# Nick_Lester_Final.net
KiCad netlist of a schematic drawn in EAGLE
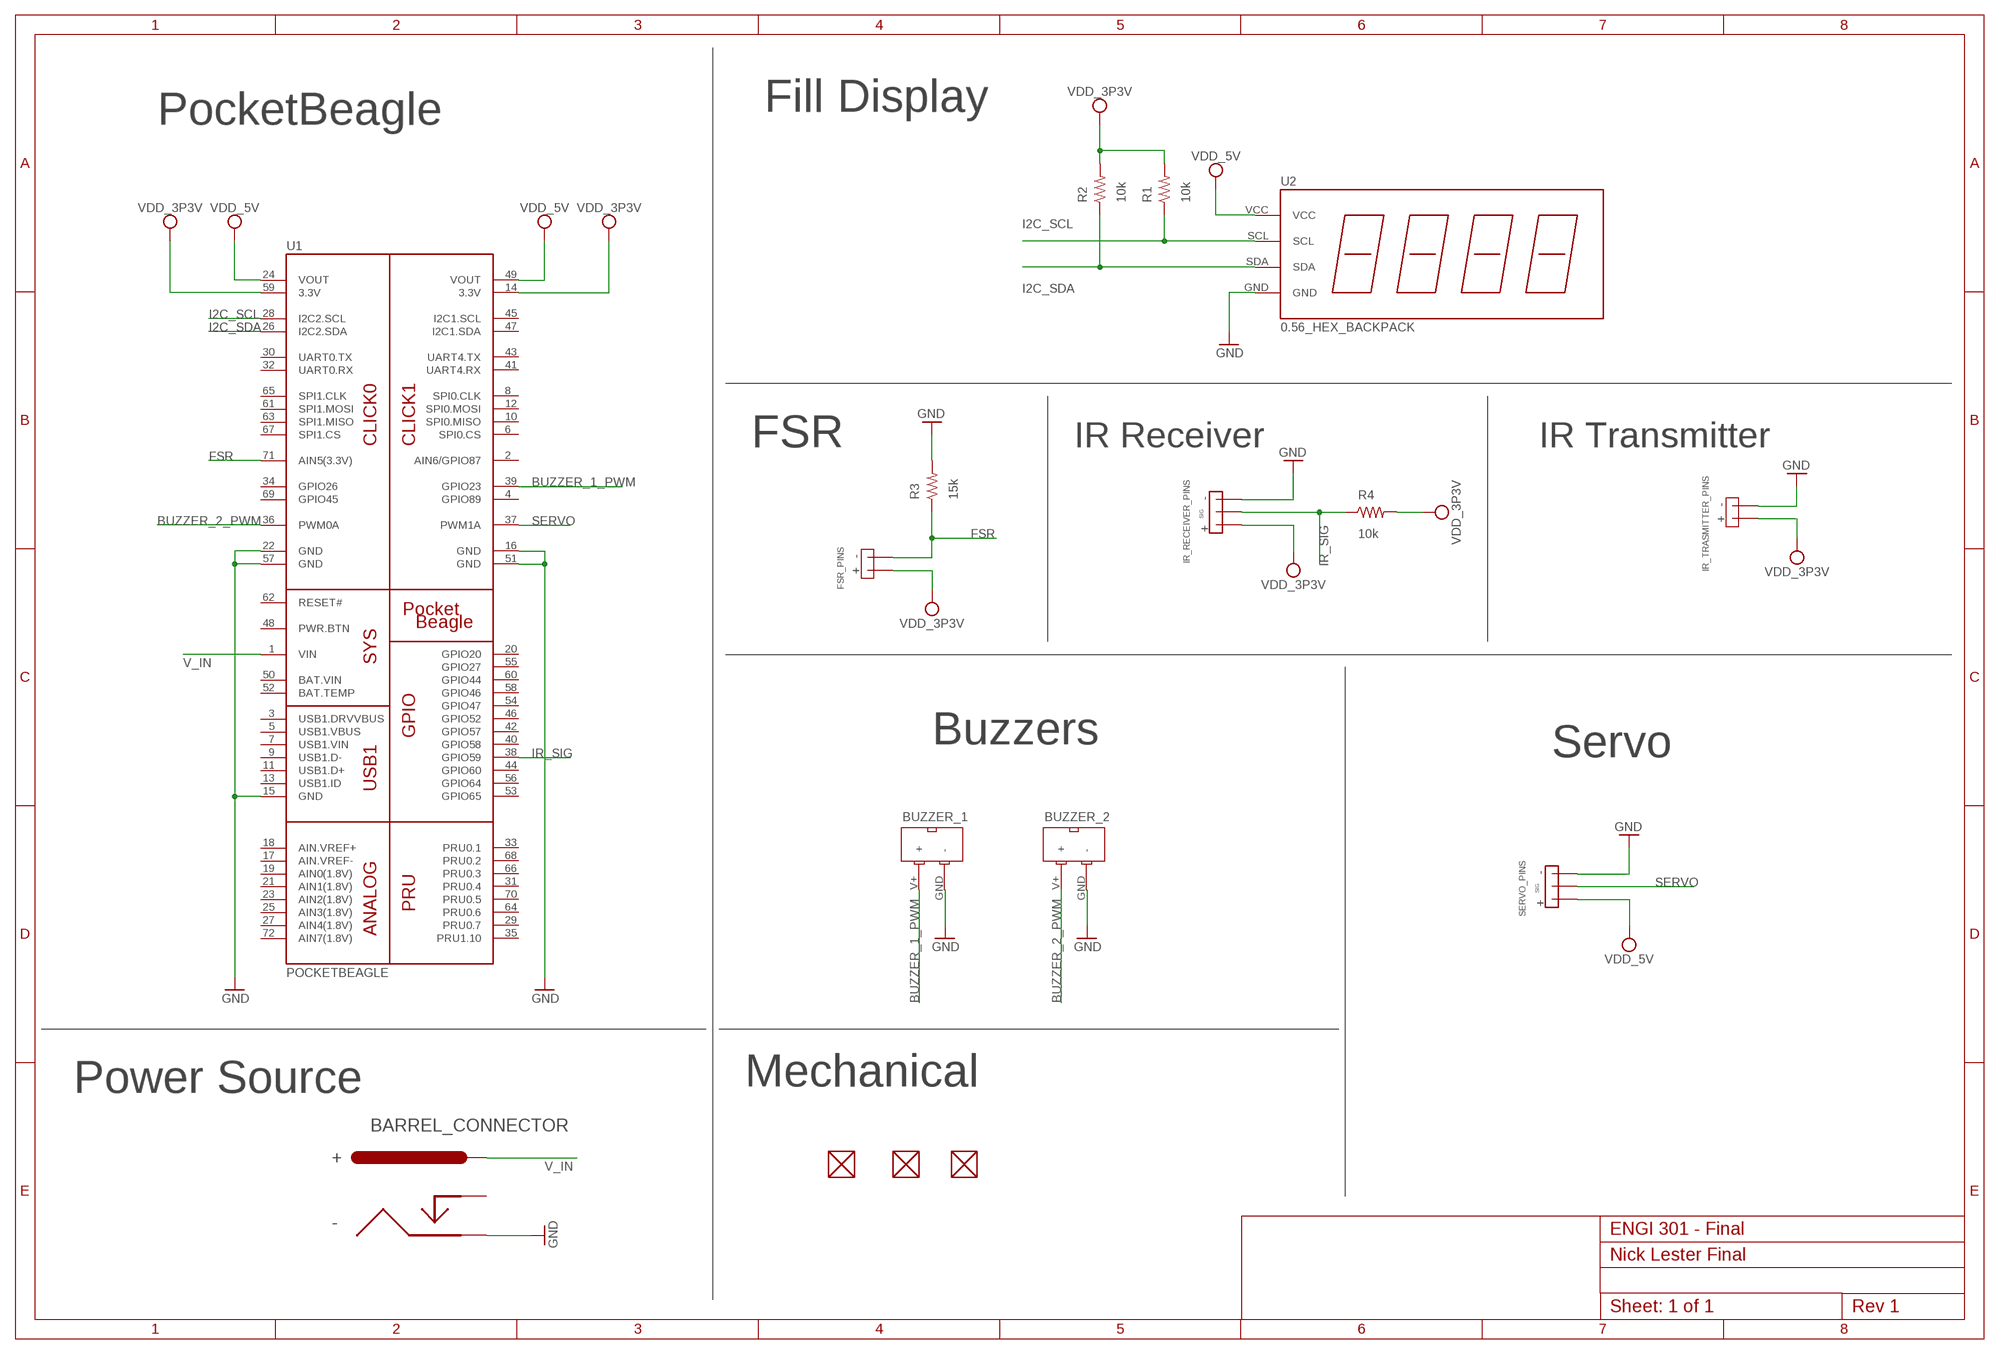
[diagram p0: schematic, sheet 1]

(export (version "E")
  (design (tool "Eeschema 10.0.6"))
  (components
    (comp (ref "BARREL_CONNECTOR")
      (value "BARREL_CONNECTOR")
      (footprint "eagle-import:BARREL_CONNECTOR")
      (libsource (lib "eagle-import") (part "BARREL_CONNECTOR"))
    )
    (comp (ref "BUZZER_1")
      (value "PS1240_BUZZER")
      (footprint "eagle-import:PS1240_BUZZER")
      (libsource (lib "eagle-import") (part "PS1240_BUZZER"))
    )
    (comp (ref "BUZZER_2")
      (value "PS1240_BUZZER")
      (footprint "eagle-import:PS1240_BUZZER")
      (libsource (lib "eagle-import") (part "PS1240_BUZZER"))
    )
    (comp (ref "FSR_PINS")
      (value "2_PIN_HEADER")
      (footprint "eagle-import:2_PIN_HEADER")
      (libsource (lib "eagle-import") (part "2_PIN_HEADER"))
    )
    (comp (ref "FUD1")
      (value "FIDUCIAL")
      (footprint "eagle-import:FIDUCIAL_40MIL")
      (libsource (lib "eagle-import") (part "FIDUCIAL"))
    )
    (comp (ref "FUD2")
      (value "FIDUCIAL")
      (footprint "eagle-import:FIDUCIAL_40MIL")
      (libsource (lib "eagle-import") (part "FIDUCIAL"))
    )
    (comp (ref "FUD3")
      (value "FIDUCIAL")
      (footprint "eagle-import:FIDUCIAL_40MIL")
      (libsource (lib "eagle-import") (part "FIDUCIAL"))
    )
    (comp (ref "IR_RECEIVER_PINS")
      (value "3_PIN_HEADER")
      (footprint "eagle-import:3_PIN_HEADER")
      (libsource (lib "eagle-import") (part "3_PIN_HEADER"))
    )
    (comp (ref "IR_TRASMITTER_PINS")
      (value "2_PIN_HEADER")
      (footprint "eagle-import:2_PIN_HEADER")
      (libsource (lib "eagle-import") (part "2_PIN_HEADER"))
    )
    (comp (ref "R1")
      (value "10k")
      (footprint "eagle-import:R0603")
      (libsource (lib "eagle-import") (part "R_R0603"))
    )
    (comp (ref "R2")
      (value "10k")
      (footprint "eagle-import:R0603")
      (libsource (lib "eagle-import") (part "R_R0603"))
    )
    (comp (ref "R3")
      (value "15k")
      (footprint "eagle-import:R0603")
      (libsource (lib "eagle-import") (part "R_R0603"))
    )
    (comp (ref "R4")
      (value "10k")
      (footprint "eagle-import:R0603")
      (libsource (lib "eagle-import") (part "R_R0603"))
    )
    (comp (ref "SERVO_PINS")
      (value "3_PIN_HEADER")
      (footprint "eagle-import:3_PIN_HEADER")
      (libsource (lib "eagle-import") (part "3_PIN_HEADER"))
    )
    (comp (ref "U1")
      (value "POCKETBEAGLE")
      (footprint "eagle-import:POCKETBEAGLE")
      (libsource (lib "eagle-import") (part "POCKETBEAGLE"))
    )
    (comp (ref "U2")
      (value "0.56_HEX_BACKPACK")
      (footprint "eagle-import:0.56_HEX_BACKPACK")
      (libsource (lib "eagle-import") (part "0.56_HEX_BACKPACK"))
    )
  )
  (nets
    (net (code "1") (name "/BAT.VIN") (class "Default")
      (node (ref "U1") (pin "50") (pinfunction "BAT.VIN_50") (pintype "power_in"))
    )
    (net (code "2") (name "/BUZZER_1_PWM") (class "Default")
      (node (ref "BUZZER_1") (pin "V+") (pinfunction "+_V+") (pintype "passive"))
      (node (ref "U1") (pin "39") (pinfunction "GPIO23_39") (pintype "bidirectional"))
    )
    (net (code "3") (name "/BUZZER_2_PWM") (class "Default")
      (node (ref "BUZZER_2") (pin "V+") (pinfunction "+_V+") (pintype "passive"))
      (node (ref "U1") (pin "36") (pinfunction "PWM0A_36") (pintype "bidirectional"))
    )
    (net (code "4") (name "/FSR") (class "Default")
      (node (ref "FSR_PINS") (pin "GND") (pinfunction "GND_GND") (pintype "bidirectional"))
      (node (ref "R3") (pin "1") (pinfunction "1_1") (pintype "passive"))
      (node (ref "U1") (pin "71") (pinfunction "AIN5(3.3V)_71") (pintype "bidirectional"))
    )
    (net (code "5") (name "/I2C_SCL") (class "Default")
      (node (ref "R1") (pin "1") (pinfunction "1_1") (pintype "passive"))
      (node (ref "U1") (pin "28") (pinfunction "I2C2.SCL_28") (pintype "bidirectional"))
      (node (ref "U2") (pin "SCL") (pinfunction "SCL_SCL") (pintype "bidirectional"))
    )
    (net (code "6") (name "/I2C_SDA") (class "Default")
      (node (ref "R2") (pin "1") (pinfunction "1_1") (pintype "passive"))
      (node (ref "U1") (pin "26") (pinfunction "I2C2.SDA_26") (pintype "bidirectional"))
      (node (ref "U2") (pin "SDA") (pinfunction "SDA_SDA") (pintype "bidirectional"))
    )
    (net (code "7") (name "/IR_SIG") (class "Default")
      (node (ref "IR_RECEIVER_PINS") (pin "SIG") (pinfunction "SIG_SIG") (pintype "bidirectional"))
      (node (ref "R4") (pin "1") (pinfunction "1_1") (pintype "passive"))
      (node (ref "U1") (pin "38") (pinfunction "GPIO59_38") (pintype "bidirectional"))
    )
    (net (code "8") (name "/SERVO") (class "Default")
      (node (ref "SERVO_PINS") (pin "SIG") (pinfunction "SIG_SIG") (pintype "bidirectional"))
      (node (ref "U1") (pin "37") (pinfunction "PWM1A_37") (pintype "bidirectional"))
    )
    (net (code "9") (name "/V_IN") (class "Default")
      (node (ref "BARREL_CONNECTOR") (pin "V+") (pinfunction "V+_V+") (pintype "output"))
      (node (ref "U1") (pin "1") (pinfunction "VIN_1") (pintype "power_in"))
    )
    (net (code "10") (name "GND") (class "Default")
      (node (ref "BARREL_CONNECTOR") (pin "GND") (pinfunction "GND_GND") (pintype "input"))
      (node (ref "BUZZER_1") (pin "GND") (pinfunction "-_GND") (pintype "passive"))
      (node (ref "BUZZER_2") (pin "GND") (pinfunction "-_GND") (pintype "passive"))
      (node (ref "IR_RECEIVER_PINS") (pin "GND") (pinfunction "GND_GND") (pintype "bidirectional"))
      (node (ref "IR_TRASMITTER_PINS") (pin "GND") (pinfunction "GND_GND") (pintype "bidirectional"))
      (node (ref "R3") (pin "2") (pinfunction "2_2") (pintype "passive"))
      (node (ref "SERVO_PINS") (pin "GND") (pinfunction "GND_GND") (pintype "bidirectional"))
      (node (ref "U1") (pin "15") (pinfunction "GND_15") (pintype "bidirectional"))
      (node (ref "U1") (pin "16") (pinfunction "GND_16") (pintype "power_in"))
      (node (ref "U1") (pin "22") (pinfunction "GND_22") (pintype "power_in"))
      (node (ref "U1") (pin "51") (pinfunction "GND_51") (pintype "power_in"))
      (node (ref "U1") (pin "57") (pinfunction "GND_57") (pintype "power_in"))
      (node (ref "U2") (pin "GND") (pinfunction "GND_GND") (pintype "bidirectional"))
    )
    (net (code "11") (name "VDD_3P3V") (class "Default")
      (node (ref "FSR_PINS") (pin "V+") (pinfunction "V+_V+") (pintype "bidirectional"))
      (node (ref "IR_RECEIVER_PINS") (pin "V+") (pinfunction "V+_V+") (pintype "bidirectional"))
      (node (ref "IR_TRASMITTER_PINS") (pin "V+") (pinfunction "V+_V+") (pintype "bidirectional"))
      (node (ref "R1") (pin "2") (pinfunction "2_2") (pintype "passive"))
      (node (ref "R2") (pin "2") (pinfunction "2_2") (pintype "passive"))
      (node (ref "R4") (pin "2") (pinfunction "2_2") (pintype "passive"))
      (node (ref "U1") (pin "14") (pinfunction "3.3V_14") (pintype "power_in"))
      (node (ref "U1") (pin "59") (pinfunction "3.3V_59") (pintype "power_in"))
    )
    (net (code "12") (name "VDD_5V") (class "Default")
      (node (ref "SERVO_PINS") (pin "V+") (pinfunction "V+_V+") (pintype "bidirectional"))
      (node (ref "U1") (pin "24") (pinfunction "VOUT_24") (pintype "power_in"))
      (node (ref "U1") (pin "49") (pinfunction "VOUT_49") (pintype "power_in"))
      (node (ref "U2") (pin "VCC") (pinfunction "VCC_VCC") (pintype "power_in"))
    )
    (net (code "13") (name "unconnected-(BARREL_CONNECTOR-PadNC)") (class "Default")
      (node (ref "BARREL_CONNECTOR") (pin "NC") (pinfunction "NC_NC") (pintype "no_connect"))
    )
    (net (code "14") (name "unconnected-(FUD1-PadP$1)") (class "Default")
      (node (ref "FUD1") (pin "P$1") (pinfunction "P$1_P$1") (pintype "no_connect"))
    )
    (net (code "15") (name "unconnected-(FUD2-PadP$1)") (class "Default")
      (node (ref "FUD2") (pin "P$1") (pinfunction "P$1_P$1") (pintype "no_connect"))
    )
    (net (code "16") (name "unconnected-(FUD3-PadP$1)") (class "Default")
      (node (ref "FUD3") (pin "P$1") (pinfunction "P$1_P$1") (pintype "no_connect"))
    )
    (net (code "17") (name "unconnected-(U1-AIN.VREF+-Pad18)") (class "Default")
      (node (ref "U1") (pin "18") (pinfunction "AIN.VREF+_18") (pintype "input"))
    )
    (net (code "18") (name "unconnected-(U1-AIN.VREF--Pad17)") (class "Default")
      (node (ref "U1") (pin "17") (pinfunction "AIN.VREF-_17") (pintype "input"))
    )
    (net (code "19") (name "unconnected-(U1-AIN0(1.8V)-Pad19)") (class "Default")
      (node (ref "U1") (pin "19") (pinfunction "AIN0(1.8V)_19") (pintype "input"))
    )
    (net (code "20") (name "unconnected-(U1-AIN1(1.8V)-Pad21)") (class "Default")
      (node (ref "U1") (pin "21") (pinfunction "AIN1(1.8V)_21") (pintype "input"))
    )
    (net (code "21") (name "unconnected-(U1-AIN2(1.8V)-Pad23)") (class "Default")
      (node (ref "U1") (pin "23") (pinfunction "AIN2(1.8V)_23") (pintype "input"))
    )
    (net (code "22") (name "unconnected-(U1-AIN3(1.8V)-Pad25)") (class "Default")
      (node (ref "U1") (pin "25") (pinfunction "AIN3(1.8V)_25") (pintype "input"))
    )
    (net (code "23") (name "unconnected-(U1-AIN4(1.8V)-Pad27)") (class "Default")
      (node (ref "U1") (pin "27") (pinfunction "AIN4(1.8V)_27") (pintype "input"))
    )
    (net (code "24") (name "unconnected-(U1-AIN6{slash}GPIO87-Pad2)") (class "Default")
      (node (ref "U1") (pin "2") (pinfunction "AIN6/GPIO87_2") (pintype "bidirectional"))
    )
    (net (code "25") (name "unconnected-(U1-AIN7(1.8V)-Pad72)") (class "Default")
      (node (ref "U1") (pin "72") (pinfunction "AIN7(1.8V)_72") (pintype "input"))
    )
    (net (code "26") (name "unconnected-(U1-BAT.TEMP-Pad52)") (class "Default")
      (node (ref "U1") (pin "52") (pinfunction "BAT.TEMP_52") (pintype "input"))
    )
    (net (code "27") (name "unconnected-(U1-GPIO20-Pad20)") (class "Default")
      (node (ref "U1") (pin "20") (pinfunction "GPIO20_20") (pintype "bidirectional"))
    )
    (net (code "28") (name "unconnected-(U1-GPIO26-Pad34)") (class "Default")
      (node (ref "U1") (pin "34") (pinfunction "GPIO26_34") (pintype "bidirectional"))
    )
    (net (code "29") (name "unconnected-(U1-GPIO27-Pad55)") (class "Default")
      (node (ref "U1") (pin "55") (pinfunction "GPIO27_55") (pintype "bidirectional"))
    )
    (net (code "30") (name "unconnected-(U1-GPIO44-Pad60)") (class "Default")
      (node (ref "U1") (pin "60") (pinfunction "GPIO44_60") (pintype "bidirectional"))
    )
    (net (code "31") (name "unconnected-(U1-GPIO45-Pad69)") (class "Default")
      (node (ref "U1") (pin "69") (pinfunction "GPIO45_69") (pintype "bidirectional"))
    )
    (net (code "32") (name "unconnected-(U1-GPIO46-Pad58)") (class "Default")
      (node (ref "U1") (pin "58") (pinfunction "GPIO46_58") (pintype "bidirectional"))
    )
    (net (code "33") (name "unconnected-(U1-GPIO47-Pad54)") (class "Default")
      (node (ref "U1") (pin "54") (pinfunction "GPIO47_54") (pintype "bidirectional"))
    )
    (net (code "34") (name "unconnected-(U1-GPIO52-Pad46)") (class "Default")
      (node (ref "U1") (pin "46") (pinfunction "GPIO52_46") (pintype "bidirectional"))
    )
    (net (code "35") (name "unconnected-(U1-GPIO57-Pad42)") (class "Default")
      (node (ref "U1") (pin "42") (pinfunction "GPIO57_42") (pintype "bidirectional"))
    )
    (net (code "36") (name "unconnected-(U1-GPIO58-Pad40)") (class "Default")
      (node (ref "U1") (pin "40") (pinfunction "GPIO58_40") (pintype "bidirectional"))
    )
    (net (code "37") (name "unconnected-(U1-GPIO60-Pad44)") (class "Default")
      (node (ref "U1") (pin "44") (pinfunction "GPIO60_44") (pintype "bidirectional"))
    )
    (net (code "38") (name "unconnected-(U1-GPIO64-Pad56)") (class "Default")
      (node (ref "U1") (pin "56") (pinfunction "GPIO64_56") (pintype "bidirectional"))
    )
    (net (code "39") (name "unconnected-(U1-GPIO65-Pad53)") (class "Default")
      (node (ref "U1") (pin "53") (pinfunction "GPIO65_53") (pintype "bidirectional"))
    )
    (net (code "40") (name "unconnected-(U1-GPIO89-Pad4)") (class "Default")
      (node (ref "U1") (pin "4") (pinfunction "GPIO89_4") (pintype "bidirectional"))
    )
    (net (code "41") (name "unconnected-(U1-I2C1.SCL-Pad45)") (class "Default")
      (node (ref "U1") (pin "45") (pinfunction "I2C1.SCL_45") (pintype "bidirectional"))
    )
    (net (code "42") (name "unconnected-(U1-I2C1.SDA-Pad47)") (class "Default")
      (node (ref "U1") (pin "47") (pinfunction "I2C1.SDA_47") (pintype "bidirectional"))
    )
    (net (code "43") (name "unconnected-(U1-PRU0.1-Pad33)") (class "Default")
      (node (ref "U1") (pin "33") (pinfunction "PRU0.1_33") (pintype "bidirectional"))
    )
    (net (code "44") (name "unconnected-(U1-PRU0.2-Pad68)") (class "Default")
      (node (ref "U1") (pin "68") (pinfunction "PRU0.2_68") (pintype "bidirectional"))
    )
    (net (code "45") (name "unconnected-(U1-PRU0.3-Pad66)") (class "Default")
      (node (ref "U1") (pin "66") (pinfunction "PRU0.3_66") (pintype "bidirectional"))
    )
    (net (code "46") (name "unconnected-(U1-PRU0.4-Pad31)") (class "Default")
      (node (ref "U1") (pin "31") (pinfunction "PRU0.4_31") (pintype "bidirectional"))
    )
    (net (code "47") (name "unconnected-(U1-PRU0.5-Pad70)") (class "Default")
      (node (ref "U1") (pin "70") (pinfunction "PRU0.5_70") (pintype "bidirectional"))
    )
    (net (code "48") (name "unconnected-(U1-PRU0.6-Pad64)") (class "Default")
      (node (ref "U1") (pin "64") (pinfunction "PRU0.6_64") (pintype "bidirectional"))
    )
    (net (code "49") (name "unconnected-(U1-PRU0.7-Pad29)") (class "Default")
      (node (ref "U1") (pin "29") (pinfunction "PRU0.7_29") (pintype "bidirectional"))
    )
    (net (code "50") (name "unconnected-(U1-PRU1.10-Pad35)") (class "Default")
      (node (ref "U1") (pin "35") (pinfunction "PRU1.10_35") (pintype "bidirectional"))
    )
    (net (code "51") (name "unconnected-(U1-PWR.BTN-Pad48)") (class "Default")
      (node (ref "U1") (pin "48") (pinfunction "PWR.BTN_48") (pintype "input"))
    )
    (net (code "52") (name "unconnected-(U1-RESET#-Pad62)") (class "Default")
      (node (ref "U1") (pin "62") (pinfunction "RESET#_62") (pintype "input"))
    )
    (net (code "53") (name "unconnected-(U1-SPI0.CLK-Pad8)") (class "Default")
      (node (ref "U1") (pin "8") (pinfunction "SPI0.CLK_8") (pintype "bidirectional"))
    )
    (net (code "54") (name "unconnected-(U1-SPI0.CS-Pad6)") (class "Default")
      (node (ref "U1") (pin "6") (pinfunction "SPI0.CS_6") (pintype "bidirectional"))
    )
    (net (code "55") (name "unconnected-(U1-SPI0.MISO-Pad10)") (class "Default")
      (node (ref "U1") (pin "10") (pinfunction "SPI0.MISO_10") (pintype "bidirectional"))
    )
    (net (code "56") (name "unconnected-(U1-SPI0.MOSI-Pad12)") (class "Default")
      (node (ref "U1") (pin "12") (pinfunction "SPI0.MOSI_12") (pintype "bidirectional"))
    )
    (net (code "57") (name "unconnected-(U1-SPI1.CLK-Pad65)") (class "Default")
      (node (ref "U1") (pin "65") (pinfunction "SPI1.CLK_65") (pintype "bidirectional"))
    )
    (net (code "58") (name "unconnected-(U1-SPI1.CS-Pad67)") (class "Default")
      (node (ref "U1") (pin "67") (pinfunction "SPI1.CS_67") (pintype "bidirectional"))
    )
    (net (code "59") (name "unconnected-(U1-SPI1.MISO-Pad63)") (class "Default")
      (node (ref "U1") (pin "63") (pinfunction "SPI1.MISO_63") (pintype "bidirectional"))
    )
    (net (code "60") (name "unconnected-(U1-SPI1.MOSI-Pad61)") (class "Default")
      (node (ref "U1") (pin "61") (pinfunction "SPI1.MOSI_61") (pintype "bidirectional"))
    )
    (net (code "61") (name "unconnected-(U1-UART0.RX-Pad32)") (class "Default")
      (node (ref "U1") (pin "32") (pinfunction "UART0.RX_32") (pintype "bidirectional"))
    )
    (net (code "62") (name "unconnected-(U1-UART0.TX-Pad30)") (class "Default")
      (node (ref "U1") (pin "30") (pinfunction "UART0.TX_30") (pintype "bidirectional"))
    )
    (net (code "63") (name "unconnected-(U1-UART4.RX-Pad41)") (class "Default")
      (node (ref "U1") (pin "41") (pinfunction "UART4.RX_41") (pintype "bidirectional"))
    )
    (net (code "64") (name "unconnected-(U1-UART4.TX-Pad43)") (class "Default")
      (node (ref "U1") (pin "43") (pinfunction "UART4.TX_43") (pintype "bidirectional"))
    )
    (net (code "65") (name "unconnected-(U1-USB1.D+-Pad11)") (class "Default")
      (node (ref "U1") (pin "11") (pinfunction "USB1.D+_11") (pintype "bidirectional"))
    )
    (net (code "66") (name "unconnected-(U1-USB1.D--Pad9)") (class "Default")
      (node (ref "U1") (pin "9") (pinfunction "USB1.D-_9") (pintype "bidirectional"))
    )
    (net (code "67") (name "unconnected-(U1-USB1.DRVVBUS-Pad3)") (class "Default")
      (node (ref "U1") (pin "3") (pinfunction "USB1.DRVVBUS_3") (pintype "bidirectional"))
    )
    (net (code "68") (name "unconnected-(U1-USB1.ID-Pad13)") (class "Default")
      (node (ref "U1") (pin "13") (pinfunction "USB1.ID_13") (pintype "bidirectional"))
    )
    (net (code "69") (name "unconnected-(U1-USB1.VBUS-Pad5)") (class "Default")
      (node (ref "U1") (pin "5") (pinfunction "USB1.VBUS_5") (pintype "bidirectional"))
    )
    (net (code "70") (name "unconnected-(U1-USB1.VIN-Pad7)") (class "Default")
      (node (ref "U1") (pin "7") (pinfunction "USB1.VIN_7") (pintype "bidirectional"))
    )
  )
)
